# Attempt1.net
KiCad netlist of a schematic drawn in EAGLE
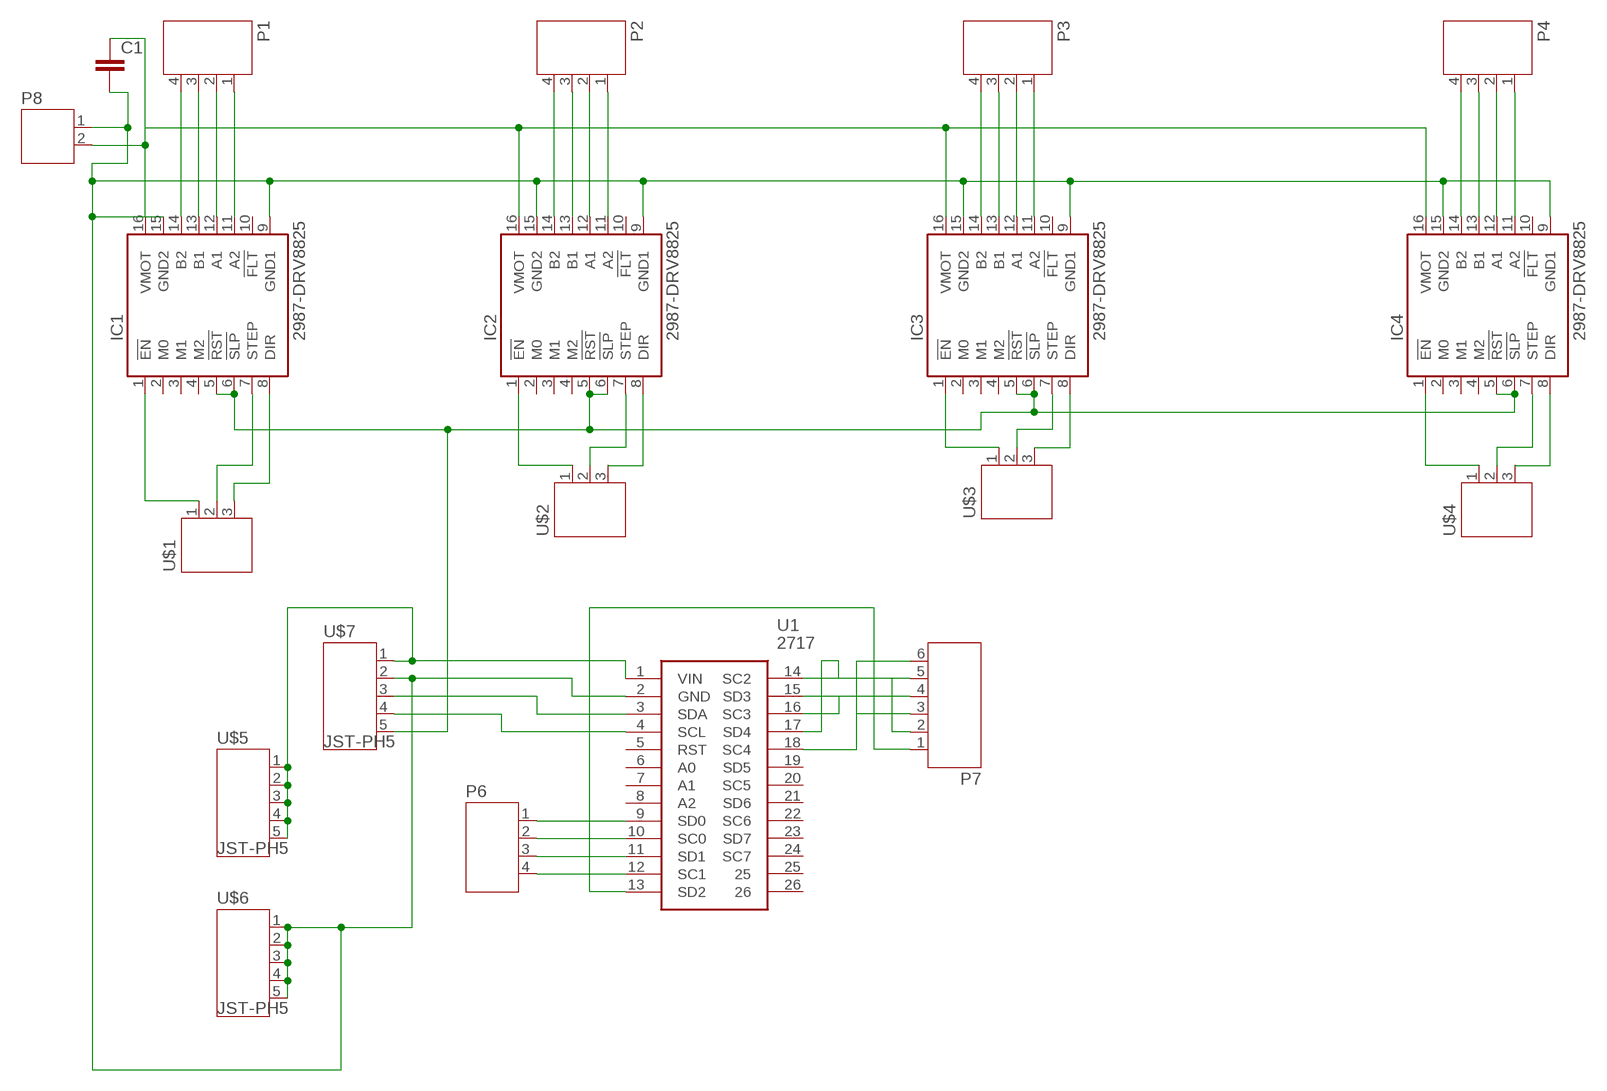
[diagram p0: schematic, sheet 1]

(export (version "E")
  (design (tool "Eeschema 10.0.6"))
  (components
    (comp (ref "C1")
      (value "C2.5/4")
      (footprint "eagle-import:C2.5-4")
      (libsource (lib "eagle-import") (part "C2.5/4"))
    )
    (comp (ref "IC1")
      (value "2987-DRV8825")
      (footprint "eagle-import:DRV8825")
      (libsource (lib "eagle-import") (part "2987-DRV8825"))
    )
    (comp (ref "IC2")
      (value "2987-DRV8825")
      (footprint "eagle-import:DRV8825")
      (libsource (lib "eagle-import") (part "2987-DRV8825"))
    )
    (comp (ref "IC3")
      (value "2987-DRV8825")
      (footprint "eagle-import:DRV8825")
      (libsource (lib "eagle-import") (part "2987-DRV8825"))
    )
    (comp (ref "IC4")
      (value "2987-DRV8825")
      (footprint "eagle-import:DRV8825")
      (libsource (lib "eagle-import") (part "2987-DRV8825"))
    )
    (comp (ref "P1")
      (value "JST-PH4")
      (footprint "eagle-import:JST-PH4")
      (libsource (lib "eagle-import") (part "JST-PH4"))
    )
    (comp (ref "P2")
      (value "JST-PH4")
      (footprint "eagle-import:JST-PH4")
      (libsource (lib "eagle-import") (part "JST-PH4"))
    )
    (comp (ref "P3")
      (value "JST-PH4")
      (footprint "eagle-import:JST-PH4")
      (libsource (lib "eagle-import") (part "JST-PH4"))
    )
    (comp (ref "P4")
      (value "JST-PH4")
      (footprint "eagle-import:JST-PH4")
      (libsource (lib "eagle-import") (part "JST-PH4"))
    )
    (comp (ref "P6")
      (value "JST-PH4")
      (footprint "eagle-import:JST-PH4")
      (libsource (lib "eagle-import") (part "JST-PH4"))
    )
    (comp (ref "P7")
      (value "JST-PH6")
      (footprint "eagle-import:JST-PH6")
      (libsource (lib "eagle-import") (part "JST-PH6"))
    )
    (comp (ref "P8")
      (value "JST-PH2")
      (footprint "eagle-import:JST-PH2")
      (libsource (lib "eagle-import") (part "JST-PH2"))
    )
    (comp (ref "U$1")
      (value "JST-PH3")
      (footprint "eagle-import:JST-PH3")
      (libsource (lib "eagle-import") (part "JST-PH3"))
    )
    (comp (ref "U$2")
      (value "JST-PH3")
      (footprint "eagle-import:JST-PH3")
      (libsource (lib "eagle-import") (part "JST-PH3"))
    )
    (comp (ref "U$3")
      (value "JST-PH3")
      (footprint "eagle-import:JST-PH3")
      (libsource (lib "eagle-import") (part "JST-PH3"))
    )
    (comp (ref "U$4")
      (value "JST-PH3")
      (footprint "eagle-import:JST-PH3")
      (libsource (lib "eagle-import") (part "JST-PH3"))
    )
    (comp (ref "U$5")
      (value "JST-PH5")
      (footprint "eagle-import:JST-PH5")
      (libsource (lib "eagle-import") (part "JST-PH5"))
    )
    (comp (ref "U$6")
      (value "JST-PH5")
      (footprint "eagle-import:JST-PH5")
      (libsource (lib "eagle-import") (part "JST-PH5"))
    )
    (comp (ref "U$7")
      (value "JST-PH5")
      (footprint "eagle-import:JST-PH5")
      (libsource (lib "eagle-import") (part "JST-PH5"))
    )
    (comp (ref "U1")
      (value "2717")
      (footprint "eagle-import:2717")
      (fields (field (name "MOUSER_PART_NUMBER") "485-2717"))
      (libsource (lib "eagle-import") (part "2717"))
    )
  )
  (nets
    (net (code "1") (name "Net-(IC1-A1)") (class "Default")
      (node (ref "IC1") (pin "12") (pinfunction "A1_12") (pintype "output"))
      (node (ref "P1") (pin "2") (pinfunction "2_2") (pintype "passive"))
    )
    (net (code "2") (name "Net-(IC1-A2)") (class "Default")
      (node (ref "IC1") (pin "11") (pinfunction "A2_11") (pintype "output"))
      (node (ref "P1") (pin "1") (pinfunction "1_1") (pintype "passive"))
    )
    (net (code "3") (name "Net-(IC1-B1)") (class "Default")
      (node (ref "IC1") (pin "13") (pinfunction "B1_13") (pintype "output"))
      (node (ref "P1") (pin "3") (pinfunction "3_3") (pintype "passive"))
    )
    (net (code "4") (name "Net-(IC1-B2)") (class "Default")
      (node (ref "IC1") (pin "14") (pinfunction "B2_14") (pintype "output"))
      (node (ref "P1") (pin "4") (pinfunction "4_4") (pintype "passive"))
    )
    (net (code "5") (name "Net-(IC1-DIR)") (class "Default")
      (node (ref "IC1") (pin "8") (pinfunction "DIR_8") (pintype "input"))
      (node (ref "U$1") (pin "3") (pinfunction "3_3") (pintype "passive"))
    )
    (net (code "6") (name "Net-(IC1-GND1)") (class "Default")
      (node (ref "C1") (pin "2") (pinfunction "2_2") (pintype "passive"))
      (node (ref "IC1") (pin "15") (pinfunction "GND2_15") (pintype "power_in"))
      (node (ref "IC1") (pin "9") (pinfunction "GND1_9") (pintype "power_in"))
      (node (ref "IC2") (pin "15") (pinfunction "GND2_15") (pintype "power_in"))
      (node (ref "IC2") (pin "9") (pinfunction "GND1_9") (pintype "power_in"))
      (node (ref "IC3") (pin "15") (pinfunction "GND2_15") (pintype "power_in"))
      (node (ref "IC3") (pin "9") (pinfunction "GND1_9") (pintype "power_in"))
      (node (ref "IC4") (pin "15") (pinfunction "GND2_15") (pintype "power_in"))
      (node (ref "IC4") (pin "9") (pinfunction "GND1_9") (pintype "power_in"))
      (node (ref "P8") (pin "1") (pinfunction "1_1") (pintype "passive"))
      (node (ref "U$6") (pin "1") (pinfunction "1_1") (pintype "passive"))
      (node (ref "U$6") (pin "2") (pinfunction "2_2") (pintype "passive"))
      (node (ref "U$6") (pin "3") (pinfunction "3_3") (pintype "passive"))
      (node (ref "U$6") (pin "4") (pinfunction "4_4") (pintype "passive"))
      (node (ref "U$6") (pin "5") (pinfunction "5_5") (pintype "passive"))
      (node (ref "U$7") (pin "2") (pinfunction "2_2") (pintype "passive"))
      (node (ref "U1") (pin "2") (pinfunction "GND_2") (pintype "bidirectional"))
    )
    (net (code "7") (name "Net-(IC1-STEP)") (class "Default")
      (node (ref "IC1") (pin "7") (pinfunction "STEP_7") (pintype "input"))
      (node (ref "U$1") (pin "2") (pinfunction "2_2") (pintype "passive"))
    )
    (net (code "8") (name "Net-(IC1-VMOT)") (class "Default")
      (node (ref "C1") (pin "1") (pinfunction "1_1") (pintype "passive"))
      (node (ref "IC1") (pin "16") (pinfunction "VMOT_16") (pintype "power_in"))
      (node (ref "IC2") (pin "16") (pinfunction "VMOT_16") (pintype "power_in"))
      (node (ref "IC3") (pin "16") (pinfunction "VMOT_16") (pintype "power_in"))
      (node (ref "IC4") (pin "16") (pinfunction "VMOT_16") (pintype "power_in"))
      (node (ref "P8") (pin "2") (pinfunction "2_2") (pintype "passive"))
    )
    (net (code "9") (name "Net-(IC1-~{EN})") (class "Default")
      (node (ref "IC1") (pin "1") (pinfunction "~{EN}_1") (pintype "passive"))
      (node (ref "U$1") (pin "1") (pinfunction "1_1") (pintype "passive"))
    )
    (net (code "10") (name "Net-(IC1-~{RST})") (class "Default")
      (node (ref "IC1") (pin "5") (pinfunction "~{RST}_5") (pintype "input"))
      (node (ref "IC1") (pin "6") (pinfunction "~{SLP}_6") (pintype "input"))
      (node (ref "IC2") (pin "5") (pinfunction "~{RST}_5") (pintype "input"))
      (node (ref "IC2") (pin "6") (pinfunction "~{SLP}_6") (pintype "input"))
      (node (ref "IC3") (pin "5") (pinfunction "~{RST}_5") (pintype "input"))
      (node (ref "IC3") (pin "6") (pinfunction "~{SLP}_6") (pintype "input"))
      (node (ref "IC4") (pin "5") (pinfunction "~{RST}_5") (pintype "input"))
      (node (ref "IC4") (pin "6") (pinfunction "~{SLP}_6") (pintype "input"))
      (node (ref "U$7") (pin "5") (pinfunction "5_5") (pintype "passive"))
    )
    (net (code "11") (name "Net-(IC2-A1)") (class "Default")
      (node (ref "IC2") (pin "12") (pinfunction "A1_12") (pintype "output"))
      (node (ref "P2") (pin "2") (pinfunction "2_2") (pintype "passive"))
    )
    (net (code "12") (name "Net-(IC2-A2)") (class "Default")
      (node (ref "IC2") (pin "11") (pinfunction "A2_11") (pintype "output"))
      (node (ref "P2") (pin "1") (pinfunction "1_1") (pintype "passive"))
    )
    (net (code "13") (name "Net-(IC2-B1)") (class "Default")
      (node (ref "IC2") (pin "13") (pinfunction "B1_13") (pintype "output"))
      (node (ref "P2") (pin "3") (pinfunction "3_3") (pintype "passive"))
    )
    (net (code "14") (name "Net-(IC2-B2)") (class "Default")
      (node (ref "IC2") (pin "14") (pinfunction "B2_14") (pintype "output"))
      (node (ref "P2") (pin "4") (pinfunction "4_4") (pintype "passive"))
    )
    (net (code "15") (name "Net-(IC2-DIR)") (class "Default")
      (node (ref "IC2") (pin "8") (pinfunction "DIR_8") (pintype "input"))
      (node (ref "U$2") (pin "3") (pinfunction "3_3") (pintype "passive"))
    )
    (net (code "16") (name "Net-(IC2-STEP)") (class "Default")
      (node (ref "IC2") (pin "7") (pinfunction "STEP_7") (pintype "input"))
      (node (ref "U$2") (pin "2") (pinfunction "2_2") (pintype "passive"))
    )
    (net (code "17") (name "Net-(IC2-~{EN})") (class "Default")
      (node (ref "IC2") (pin "1") (pinfunction "~{EN}_1") (pintype "passive"))
      (node (ref "U$2") (pin "1") (pinfunction "1_1") (pintype "passive"))
    )
    (net (code "18") (name "Net-(IC3-A1)") (class "Default")
      (node (ref "IC3") (pin "12") (pinfunction "A1_12") (pintype "output"))
      (node (ref "P3") (pin "2") (pinfunction "2_2") (pintype "passive"))
    )
    (net (code "19") (name "Net-(IC3-A2)") (class "Default")
      (node (ref "IC3") (pin "11") (pinfunction "A2_11") (pintype "output"))
      (node (ref "P3") (pin "1") (pinfunction "1_1") (pintype "passive"))
    )
    (net (code "20") (name "Net-(IC3-B1)") (class "Default")
      (node (ref "IC3") (pin "13") (pinfunction "B1_13") (pintype "output"))
      (node (ref "P3") (pin "3") (pinfunction "3_3") (pintype "passive"))
    )
    (net (code "21") (name "Net-(IC3-B2)") (class "Default")
      (node (ref "IC3") (pin "14") (pinfunction "B2_14") (pintype "output"))
      (node (ref "P3") (pin "4") (pinfunction "4_4") (pintype "passive"))
    )
    (net (code "22") (name "Net-(IC3-DIR)") (class "Default")
      (node (ref "IC3") (pin "8") (pinfunction "DIR_8") (pintype "input"))
      (node (ref "U$3") (pin "3") (pinfunction "3_3") (pintype "passive"))
    )
    (net (code "23") (name "Net-(IC3-STEP)") (class "Default")
      (node (ref "IC3") (pin "7") (pinfunction "STEP_7") (pintype "input"))
      (node (ref "U$3") (pin "2") (pinfunction "2_2") (pintype "passive"))
    )
    (net (code "24") (name "Net-(IC3-~{EN})") (class "Default")
      (node (ref "IC3") (pin "1") (pinfunction "~{EN}_1") (pintype "passive"))
      (node (ref "U$3") (pin "1") (pinfunction "1_1") (pintype "passive"))
    )
    (net (code "25") (name "Net-(IC4-A1)") (class "Default")
      (node (ref "IC4") (pin "12") (pinfunction "A1_12") (pintype "output"))
      (node (ref "P4") (pin "2") (pinfunction "2_2") (pintype "passive"))
    )
    (net (code "26") (name "Net-(IC4-A2)") (class "Default")
      (node (ref "IC4") (pin "11") (pinfunction "A2_11") (pintype "output"))
      (node (ref "P4") (pin "1") (pinfunction "1_1") (pintype "passive"))
    )
    (net (code "27") (name "Net-(IC4-B1)") (class "Default")
      (node (ref "IC4") (pin "13") (pinfunction "B1_13") (pintype "output"))
      (node (ref "P4") (pin "3") (pinfunction "3_3") (pintype "passive"))
    )
    (net (code "28") (name "Net-(IC4-B2)") (class "Default")
      (node (ref "IC4") (pin "14") (pinfunction "B2_14") (pintype "output"))
      (node (ref "P4") (pin "4") (pinfunction "4_4") (pintype "passive"))
    )
    (net (code "29") (name "Net-(IC4-DIR)") (class "Default")
      (node (ref "IC4") (pin "8") (pinfunction "DIR_8") (pintype "input"))
      (node (ref "U$4") (pin "3") (pinfunction "3_3") (pintype "passive"))
    )
    (net (code "30") (name "Net-(IC4-STEP)") (class "Default")
      (node (ref "IC4") (pin "7") (pinfunction "STEP_7") (pintype "input"))
      (node (ref "U$4") (pin "2") (pinfunction "2_2") (pintype "passive"))
    )
    (net (code "31") (name "Net-(IC4-~{EN})") (class "Default")
      (node (ref "IC4") (pin "1") (pinfunction "~{EN}_1") (pintype "passive"))
      (node (ref "U$4") (pin "1") (pinfunction "1_1") (pintype "passive"))
    )
    (net (code "32") (name "Net-(U1-SC0)") (class "Default")
      (node (ref "P6") (pin "2") (pinfunction "2_2") (pintype "passive"))
      (node (ref "U1") (pin "10") (pinfunction "SC0_10") (pintype "bidirectional"))
    )
    (net (code "33") (name "Net-(U1-SC1)") (class "Default")
      (node (ref "P6") (pin "4") (pinfunction "4_4") (pintype "passive"))
      (node (ref "U1") (pin "12") (pinfunction "SC1_12") (pintype "bidirectional"))
    )
    (net (code "34") (name "Net-(U1-SC2)") (class "Default")
      (node (ref "P7") (pin "2") (pinfunction "2_2") (pintype "passive"))
      (node (ref "U1") (pin "14") (pinfunction "SC2_14") (pintype "bidirectional"))
    )
    (net (code "35") (name "Net-(U1-SC3)") (class "Default")
      (node (ref "P7") (pin "4") (pinfunction "4_4") (pintype "passive"))
      (node (ref "U1") (pin "16") (pinfunction "SC3_16") (pintype "bidirectional"))
    )
    (net (code "36") (name "Net-(U1-SC4)") (class "Default")
      (node (ref "P7") (pin "6") (pinfunction "6_6") (pintype "passive"))
      (node (ref "U1") (pin "18") (pinfunction "SC4_18") (pintype "bidirectional"))
    )
    (net (code "37") (name "Net-(U1-SCL)") (class "Default")
      (node (ref "U$7") (pin "4") (pinfunction "4_4") (pintype "passive"))
      (node (ref "U1") (pin "4") (pinfunction "SCL_4") (pintype "bidirectional"))
    )
    (net (code "38") (name "Net-(U1-SD0)") (class "Default")
      (node (ref "P6") (pin "1") (pinfunction "1_1") (pintype "passive"))
      (node (ref "U1") (pin "9") (pinfunction "SD0_9") (pintype "bidirectional"))
    )
    (net (code "39") (name "Net-(U1-SD1)") (class "Default")
      (node (ref "P6") (pin "3") (pinfunction "3_3") (pintype "passive"))
      (node (ref "U1") (pin "11") (pinfunction "SD1_11") (pintype "bidirectional"))
    )
    (net (code "40") (name "Net-(U1-SD2)") (class "Default")
      (node (ref "P7") (pin "1") (pinfunction "1_1") (pintype "passive"))
      (node (ref "U1") (pin "13") (pinfunction "SD2_13") (pintype "bidirectional"))
    )
    (net (code "41") (name "Net-(U1-SD3)") (class "Default")
      (node (ref "P7") (pin "3") (pinfunction "3_3") (pintype "passive"))
      (node (ref "U1") (pin "15") (pinfunction "SD3_15") (pintype "bidirectional"))
    )
    (net (code "42") (name "Net-(U1-SD4)") (class "Default")
      (node (ref "P7") (pin "5") (pinfunction "5_5") (pintype "passive"))
      (node (ref "U1") (pin "17") (pinfunction "SD4_17") (pintype "bidirectional"))
    )
    (net (code "43") (name "Net-(U1-SDA)") (class "Default")
      (node (ref "U$7") (pin "3") (pinfunction "3_3") (pintype "passive"))
      (node (ref "U1") (pin "3") (pinfunction "SDA_3") (pintype "bidirectional"))
    )
    (net (code "44") (name "Net-(U1-VIN)") (class "Default")
      (node (ref "U$5") (pin "1") (pinfunction "1_1") (pintype "passive"))
      (node (ref "U$5") (pin "2") (pinfunction "2_2") (pintype "passive"))
      (node (ref "U$5") (pin "3") (pinfunction "3_3") (pintype "passive"))
      (node (ref "U$5") (pin "4") (pinfunction "4_4") (pintype "passive"))
      (node (ref "U$5") (pin "5") (pinfunction "5_5") (pintype "passive"))
      (node (ref "U$7") (pin "1") (pinfunction "1_1") (pintype "passive"))
      (node (ref "U1") (pin "1") (pinfunction "VIN_1") (pintype "bidirectional"))
    )
    (net (code "45") (name "unconnected-(IC1-M0-Pad2)") (class "Default")
      (node (ref "IC1") (pin "2") (pinfunction "M0_2") (pintype "passive"))
    )
    (net (code "46") (name "unconnected-(IC1-M1-Pad3)") (class "Default")
      (node (ref "IC1") (pin "3") (pinfunction "M1_3") (pintype "passive"))
    )
    (net (code "47") (name "unconnected-(IC1-M2-Pad4)") (class "Default")
      (node (ref "IC1") (pin "4") (pinfunction "M2_4") (pintype "passive"))
    )
    (net (code "48") (name "unconnected-(IC1-~{FLT}-Pad10)") (class "Default")
      (node (ref "IC1") (pin "10") (pinfunction "~{FLT}_10") (pintype "open_collector"))
    )
    (net (code "49") (name "unconnected-(IC2-M0-Pad2)") (class "Default")
      (node (ref "IC2") (pin "2") (pinfunction "M0_2") (pintype "passive"))
    )
    (net (code "50") (name "unconnected-(IC2-M1-Pad3)") (class "Default")
      (node (ref "IC2") (pin "3") (pinfunction "M1_3") (pintype "passive"))
    )
    (net (code "51") (name "unconnected-(IC2-M2-Pad4)") (class "Default")
      (node (ref "IC2") (pin "4") (pinfunction "M2_4") (pintype "passive"))
    )
    (net (code "52") (name "unconnected-(IC2-~{FLT}-Pad10)") (class "Default")
      (node (ref "IC2") (pin "10") (pinfunction "~{FLT}_10") (pintype "open_collector"))
    )
    (net (code "53") (name "unconnected-(IC3-M0-Pad2)") (class "Default")
      (node (ref "IC3") (pin "2") (pinfunction "M0_2") (pintype "passive"))
    )
    (net (code "54") (name "unconnected-(IC3-M1-Pad3)") (class "Default")
      (node (ref "IC3") (pin "3") (pinfunction "M1_3") (pintype "passive"))
    )
    (net (code "55") (name "unconnected-(IC3-M2-Pad4)") (class "Default")
      (node (ref "IC3") (pin "4") (pinfunction "M2_4") (pintype "passive"))
    )
    (net (code "56") (name "unconnected-(IC3-~{FLT}-Pad10)") (class "Default")
      (node (ref "IC3") (pin "10") (pinfunction "~{FLT}_10") (pintype "open_collector"))
    )
    (net (code "57") (name "unconnected-(IC4-M0-Pad2)") (class "Default")
      (node (ref "IC4") (pin "2") (pinfunction "M0_2") (pintype "passive"))
    )
    (net (code "58") (name "unconnected-(IC4-M1-Pad3)") (class "Default")
      (node (ref "IC4") (pin "3") (pinfunction "M1_3") (pintype "passive"))
    )
    (net (code "59") (name "unconnected-(IC4-M2-Pad4)") (class "Default")
      (node (ref "IC4") (pin "4") (pinfunction "M2_4") (pintype "passive"))
    )
    (net (code "60") (name "unconnected-(IC4-~{FLT}-Pad10)") (class "Default")
      (node (ref "IC4") (pin "10") (pinfunction "~{FLT}_10") (pintype "open_collector"))
    )
    (net (code "61") (name "unconnected-(U1-A0-Pad6)") (class "Default")
      (node (ref "U1") (pin "6") (pinfunction "A0_6") (pintype "bidirectional"))
    )
    (net (code "62") (name "unconnected-(U1-A1-Pad7)") (class "Default")
      (node (ref "U1") (pin "7") (pinfunction "A1_7") (pintype "bidirectional"))
    )
    (net (code "63") (name "unconnected-(U1-A2-Pad8)") (class "Default")
      (node (ref "U1") (pin "8") (pinfunction "A2_8") (pintype "bidirectional"))
    )
    (net (code "64") (name "unconnected-(U1-Pad25)") (class "Default")
      (node (ref "U1") (pin "25") (pinfunction "25_25") (pintype "bidirectional"))
    )
    (net (code "65") (name "unconnected-(U1-Pad26)") (class "Default")
      (node (ref "U1") (pin "26") (pinfunction "26_26") (pintype "bidirectional"))
    )
    (net (code "66") (name "unconnected-(U1-RST-Pad5)") (class "Default")
      (node (ref "U1") (pin "5") (pinfunction "RST_5") (pintype "bidirectional"))
    )
    (net (code "67") (name "unconnected-(U1-SC5-Pad20)") (class "Default")
      (node (ref "U1") (pin "20") (pinfunction "SC5_20") (pintype "bidirectional"))
    )
    (net (code "68") (name "unconnected-(U1-SC6-Pad22)") (class "Default")
      (node (ref "U1") (pin "22") (pinfunction "SC6_22") (pintype "bidirectional"))
    )
    (net (code "69") (name "unconnected-(U1-SC7-Pad24)") (class "Default")
      (node (ref "U1") (pin "24") (pinfunction "SC7_24") (pintype "bidirectional"))
    )
    (net (code "70") (name "unconnected-(U1-SD5-Pad19)") (class "Default")
      (node (ref "U1") (pin "19") (pinfunction "SD5_19") (pintype "bidirectional"))
    )
    (net (code "71") (name "unconnected-(U1-SD6-Pad21)") (class "Default")
      (node (ref "U1") (pin "21") (pinfunction "SD6_21") (pintype "bidirectional"))
    )
    (net (code "72") (name "unconnected-(U1-SD7-Pad23)") (class "Default")
      (node (ref "U1") (pin "23") (pinfunction "SD7_23") (pintype "bidirectional"))
    )
  )
)
